# 1541-3m.net
KiCad netlist of a schematic drawn in EAGLE
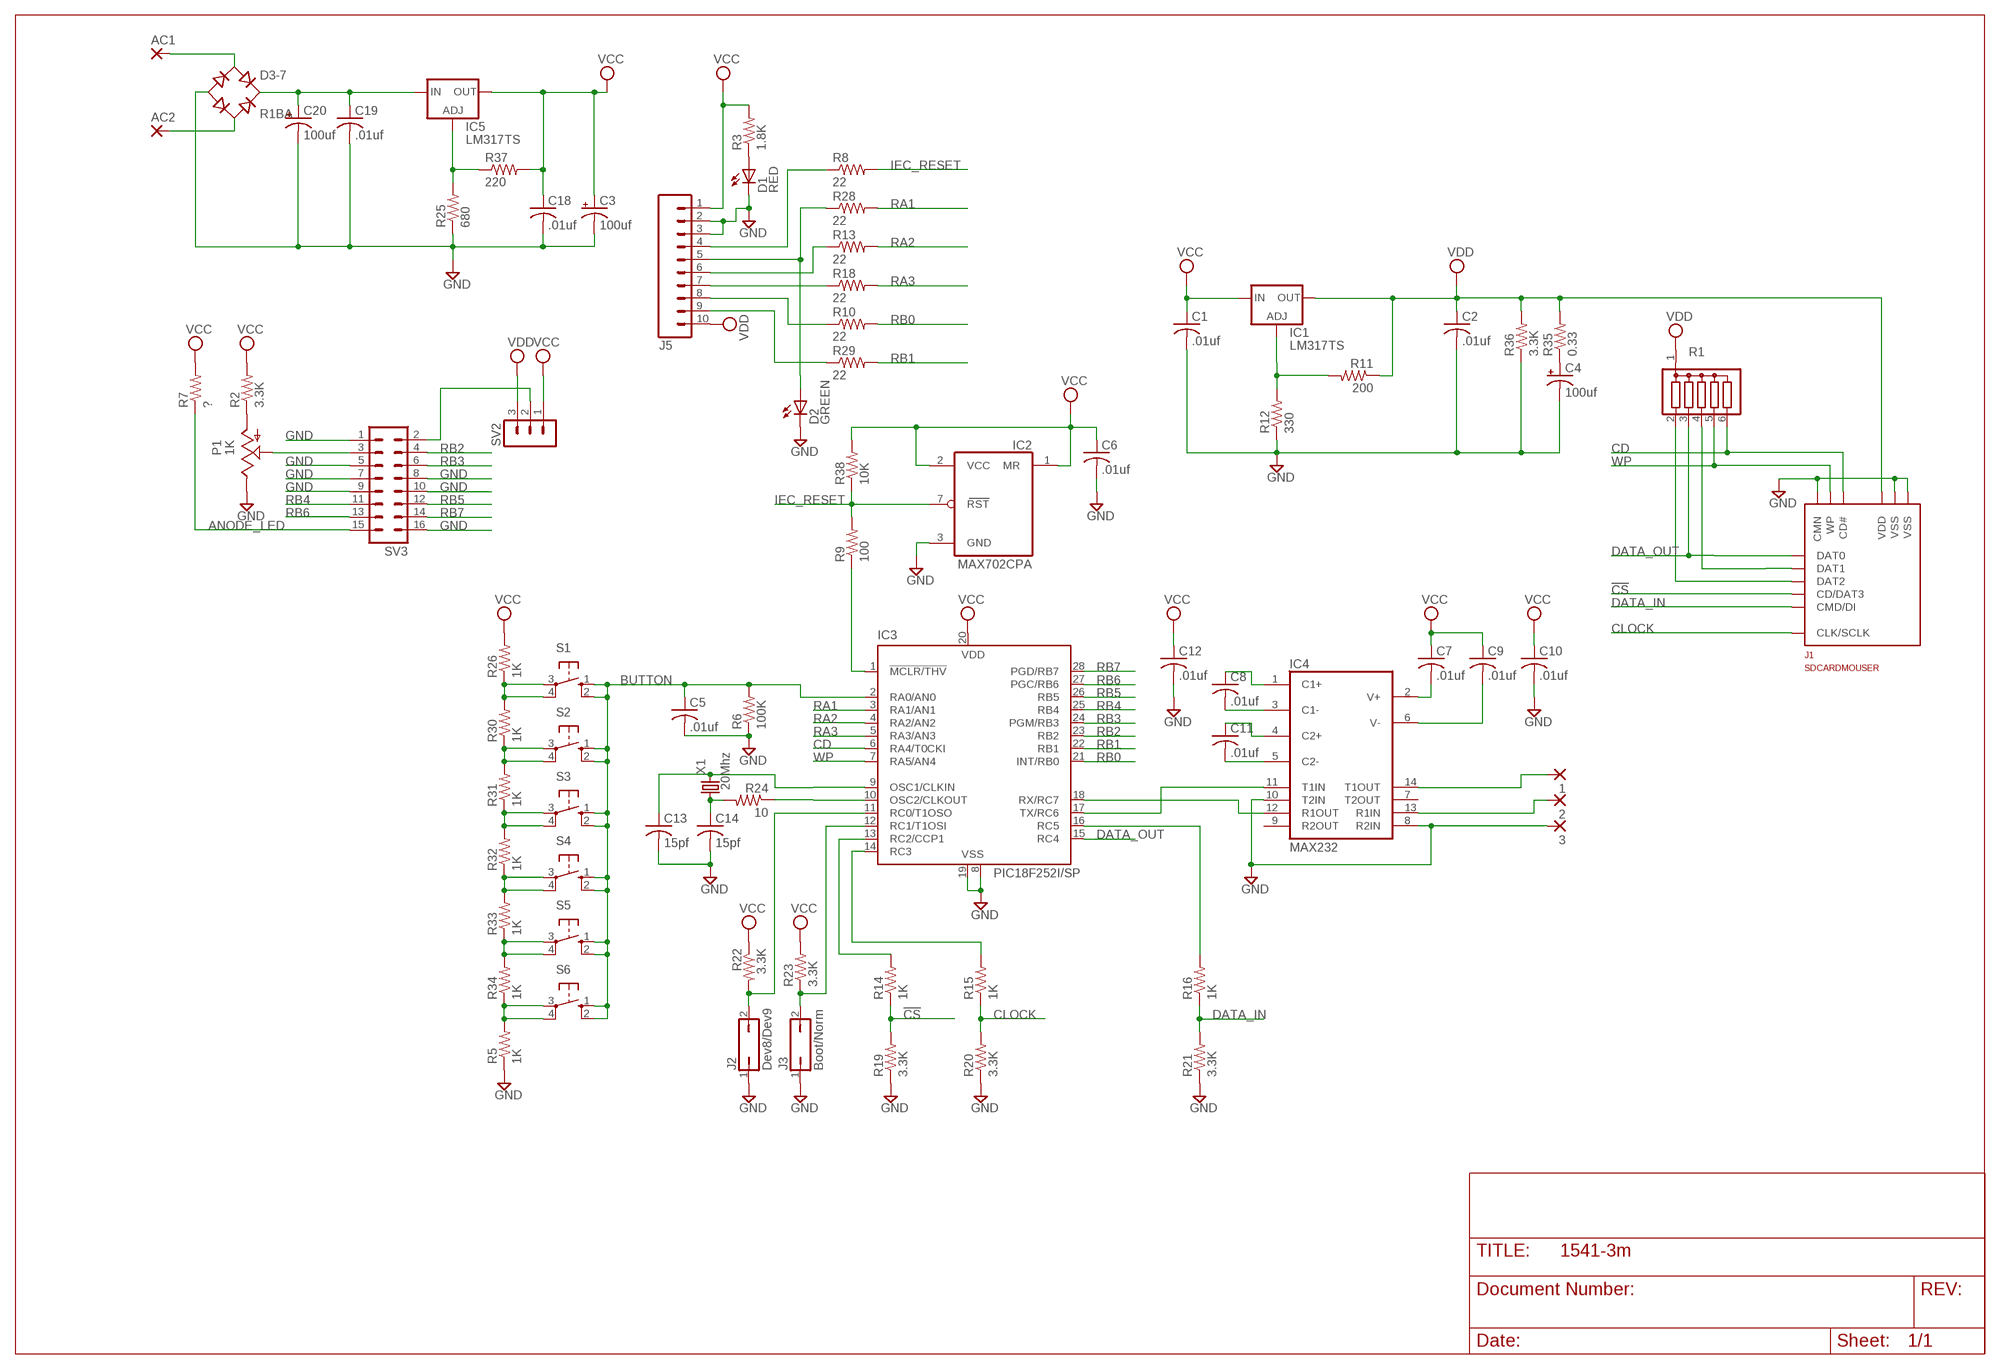
[diagram p0: schematic, sheet 1]

(export (version "E")
  (design (tool "Eeschema 10.0.6"))
  (components
    (comp (ref "1")
      (value "2,15/1,0")
      (footprint "eagle-import:2,15_1,0")
      (libsource (lib "eagle-import") (part "2,15/1,0"))
    )
    (comp (ref "2")
      (value "2,15/1,0")
      (footprint "eagle-import:2,15_1,0")
      (libsource (lib "eagle-import") (part "2,15/1,0"))
    )
    (comp (ref "3")
      (value "2,15/1,0")
      (footprint "eagle-import:2,15_1,0")
      (libsource (lib "eagle-import") (part "2,15/1,0"))
    )
    (comp (ref "AC1")
      (value "2,15/1,0")
      (footprint "eagle-import:2,15_1,0")
      (libsource (lib "eagle-import") (part "2,15/1,0"))
    )
    (comp (ref "AC2")
      (value "2,15/1,0")
      (footprint "eagle-import:2,15_1,0")
      (libsource (lib "eagle-import") (part "2,15/1,0"))
    )
    (comp (ref "C1")
      (value ".01uf")
      (footprint "eagle-import:C025-024X044")
      (libsource (lib "eagle-import") (part "C-US025-024X044"))
    )
    (comp (ref "C2")
      (value ".01uf")
      (footprint "eagle-import:C025-024X044")
      (libsource (lib "eagle-import") (part "C-US025-024X044"))
    )
    (comp (ref "C3")
      (value "100uf")
      (footprint "eagle-import:E2-5")
      (libsource (lib "eagle-import") (part "CPOL-USE2-5"))
    )
    (comp (ref "C4")
      (value "100uf")
      (footprint "eagle-import:E2-5")
      (libsource (lib "eagle-import") (part "CPOL-USE2-5"))
    )
    (comp (ref "C5")
      (value ".01uf")
      (footprint "eagle-import:C025-024X044")
      (libsource (lib "eagle-import") (part "C-US025-024X044"))
    )
    (comp (ref "C6")
      (value ".01uf")
      (footprint "eagle-import:C025-024X044")
      (libsource (lib "eagle-import") (part "C-US025-024X044"))
    )
    (comp (ref "C7")
      (value ".01uf")
      (footprint "eagle-import:C025-024X044")
      (libsource (lib "eagle-import") (part "C-US025-024X044"))
    )
    (comp (ref "C8")
      (value ".01uf")
      (footprint "eagle-import:C025-024X044")
      (libsource (lib "eagle-import") (part "C-US025-024X044"))
    )
    (comp (ref "C9")
      (value ".01uf")
      (footprint "eagle-import:C025-024X044")
      (libsource (lib "eagle-import") (part "C-US025-024X044"))
    )
    (comp (ref "C10")
      (value ".01uf")
      (footprint "eagle-import:C025-024X044")
      (libsource (lib "eagle-import") (part "C-US025-024X044"))
    )
    (comp (ref "C11")
      (value ".01uf")
      (footprint "eagle-import:C025-024X044")
      (libsource (lib "eagle-import") (part "C-US025-024X044"))
    )
    (comp (ref "C12")
      (value ".01uf")
      (footprint "eagle-import:C025-024X044")
      (libsource (lib "eagle-import") (part "C-US025-024X044"))
    )
    (comp (ref "C13")
      (value "15pf")
      (footprint "eagle-import:C025-024X044")
      (libsource (lib "eagle-import") (part "C-US025-024X044"))
    )
    (comp (ref "C14")
      (value "15pf")
      (footprint "eagle-import:C025-024X044")
      (libsource (lib "eagle-import") (part "C-US025-024X044"))
    )
    (comp (ref "C18")
      (value ".01uf")
      (footprint "eagle-import:C025-024X044")
      (libsource (lib "eagle-import") (part "C-US025-024X044"))
    )
    (comp (ref "C19")
      (value ".01uf")
      (footprint "eagle-import:C025-024X044")
      (libsource (lib "eagle-import") (part "C-US025-024X044"))
    )
    (comp (ref "C20")
      (value "100uf")
      (footprint "eagle-import:E2-5")
      (libsource (lib "eagle-import") (part "CPOL-USE2-5"))
    )
    (comp (ref "D1")
      (value "RED")
      (footprint "eagle-import:LED3MM")
      (libsource (lib "eagle-import") (part "LED3MM"))
    )
    (comp (ref "D2")
      (value "GREEN")
      (footprint "eagle-import:LED3MM")
      (libsource (lib "eagle-import") (part "LED3MM"))
    )
    (comp (ref "D3-7")
      (value "R1BA")
      (footprint "eagle-import:RB1A")
      (libsource (lib "eagle-import") (part "RB1A"))
    )
    (comp (ref "IC1")
      (value "LM317TS")
      (footprint "eagle-import:317TS")
      (libsource (lib "eagle-import") (part "LM317TS"))
    )
    (comp (ref "IC2")
      (value "MAX702CPA")
      (footprint "eagle-import:DIL08")
      (fields (field (name "MF") "MAXIM") (field (name "MPN") "MAX702CPA+"))
      (libsource (lib "eagle-import") (part "MAX702CPA"))
    )
    (comp (ref "IC3")
      (value "PIC18F252I/SP")
      (footprint "eagle-import:DIL28-3")
      (fields (field (name "MF") "MICROCHIP") (field (name "MPN") "PIC16F870-I/SP"))
      (libsource (lib "eagle-import") (part "PIC16870PF"))
    )
    (comp (ref "IC4")
      (value "MAX232")
      (footprint "eagle-import:DIL16")
      (fields (field (name "MF") "MAXIM") (field (name "MPN") "MAX232ACPE+"))
      (libsource (lib "eagle-import") (part "MAX232"))
    )
    (comp (ref "IC5")
      (value "LM317TS")
      (footprint "eagle-import:317TS")
      (libsource (lib "eagle-import") (part "LM317TS"))
    )
    (comp (ref "J1")
      (value "SDCARDMOUSER")
      (footprint "eagle-import:SCDA1A")
      (libsource (lib "eagle-import") (part "SDCARDMOUSER"))
    )
    (comp (ref "J2")
      (value "Dev8/Dev9")
      (footprint "eagle-import:JP1")
      (libsource (lib "eagle-import") (part "JP1Q"))
    )
    (comp (ref "J3")
      (value "Boot/Norm")
      (footprint "eagle-import:JP1")
      (libsource (lib "eagle-import") (part "JP1Q"))
    )
    (comp (ref "J5")
      (value "M10")
      (footprint "eagle-import:10P")
      (libsource (lib "eagle-import") (part "M10"))
    )
    (comp (ref "P1")
      (value "1K")
      (footprint "eagle-import:LI10")
      (libsource (lib "eagle-import") (part "TRIM_US-LI10"))
    )
    (comp (ref "R1")
      (value "G05R")
      (footprint "eagle-import:SIL6")
      (libsource (lib "eagle-import") (part "G05R"))
    )
    (comp (ref "R2")
      (value "3.3K")
      (footprint "eagle-import:0207_2V")
      (libsource (lib "eagle-import") (part "R-US_0207/2V"))
    )
    (comp (ref "R3")
      (value "1.8K")
      (footprint "eagle-import:0207_2V")
      (libsource (lib "eagle-import") (part "R-US_0207/2V"))
    )
    (comp (ref "R5")
      (value "1K")
      (footprint "eagle-import:0207_2V")
      (libsource (lib "eagle-import") (part "R-US_0207/2V"))
    )
    (comp (ref "R6")
      (value "100K")
      (footprint "eagle-import:0207_2V")
      (libsource (lib "eagle-import") (part "R-US_0207/2V"))
    )
    (comp (ref "R7")
      (value "?")
      (footprint "eagle-import:0207_2V")
      (libsource (lib "eagle-import") (part "R-US_0207/2V"))
    )
    (comp (ref "R8")
      (value "22")
      (footprint "eagle-import:0207_2V")
      (libsource (lib "eagle-import") (part "R-US_0207/2V"))
    )
    (comp (ref "R9")
      (value "100")
      (footprint "eagle-import:0207_2V")
      (libsource (lib "eagle-import") (part "R-US_0207/2V"))
    )
    (comp (ref "R10")
      (value "22")
      (footprint "eagle-import:0207_2V")
      (libsource (lib "eagle-import") (part "R-US_0207/2V"))
    )
    (comp (ref "R11")
      (value "200")
      (footprint "eagle-import:0207_2V")
      (libsource (lib "eagle-import") (part "R-US_0207/2V"))
    )
    (comp (ref "R12")
      (value "330")
      (footprint "eagle-import:0207_2V")
      (libsource (lib "eagle-import") (part "R-US_0207/2V"))
    )
    (comp (ref "R13")
      (value "22")
      (footprint "eagle-import:0207_2V")
      (libsource (lib "eagle-import") (part "R-US_0207/2V"))
    )
    (comp (ref "R14")
      (value "1K")
      (footprint "eagle-import:0207_2V")
      (libsource (lib "eagle-import") (part "R-US_0207/2V"))
    )
    (comp (ref "R15")
      (value "1K")
      (footprint "eagle-import:0207_2V")
      (libsource (lib "eagle-import") (part "R-US_0207/2V"))
    )
    (comp (ref "R16")
      (value "1K")
      (footprint "eagle-import:0207_2V")
      (libsource (lib "eagle-import") (part "R-US_0207/2V"))
    )
    (comp (ref "R18")
      (value "22")
      (footprint "eagle-import:0207_2V")
      (libsource (lib "eagle-import") (part "R-US_0207/2V"))
    )
    (comp (ref "R19")
      (value "3.3K")
      (footprint "eagle-import:0207_2V")
      (libsource (lib "eagle-import") (part "R-US_0207/2V"))
    )
    (comp (ref "R20")
      (value "3.3K")
      (footprint "eagle-import:0207_2V")
      (libsource (lib "eagle-import") (part "R-US_0207/2V"))
    )
    (comp (ref "R21")
      (value "3.3K")
      (footprint "eagle-import:0207_2V")
      (libsource (lib "eagle-import") (part "R-US_0207/2V"))
    )
    (comp (ref "R22")
      (value "3.3K")
      (footprint "eagle-import:0207_2V")
      (libsource (lib "eagle-import") (part "R-US_0207/2V"))
    )
    (comp (ref "R23")
      (value "3.3K")
      (footprint "eagle-import:0207_2V")
      (libsource (lib "eagle-import") (part "R-US_0207/2V"))
    )
    (comp (ref "R24")
      (value "10")
      (footprint "eagle-import:0207_2V")
      (libsource (lib "eagle-import") (part "R-US_0207/2V"))
    )
    (comp (ref "R25")
      (value "680")
      (footprint "eagle-import:0207_2V")
      (libsource (lib "eagle-import") (part "R-US_0207/2V"))
    )
    (comp (ref "R26")
      (value "1K")
      (footprint "eagle-import:0207_2V")
      (libsource (lib "eagle-import") (part "R-US_0207/2V"))
    )
    (comp (ref "R28")
      (value "22")
      (footprint "eagle-import:0207_2V")
      (libsource (lib "eagle-import") (part "R-US_0207/2V"))
    )
    (comp (ref "R29")
      (value "22")
      (footprint "eagle-import:0207_2V")
      (libsource (lib "eagle-import") (part "R-US_0207/2V"))
    )
    (comp (ref "R30")
      (value "1K")
      (footprint "eagle-import:0207_2V")
      (libsource (lib "eagle-import") (part "R-US_0207/2V"))
    )
    (comp (ref "R31")
      (value "1K")
      (footprint "eagle-import:0207_2V")
      (libsource (lib "eagle-import") (part "R-US_0207/2V"))
    )
    (comp (ref "R32")
      (value "1K")
      (footprint "eagle-import:0207_2V")
      (libsource (lib "eagle-import") (part "R-US_0207/2V"))
    )
    (comp (ref "R33")
      (value "1K")
      (footprint "eagle-import:0207_2V")
      (libsource (lib "eagle-import") (part "R-US_0207/2V"))
    )
    (comp (ref "R34")
      (value "1K")
      (footprint "eagle-import:0207_2V")
      (libsource (lib "eagle-import") (part "R-US_0207/2V"))
    )
    (comp (ref "R35")
      (value "0.33")
      (footprint "eagle-import:0207_2V")
      (libsource (lib "eagle-import") (part "R-US_0207/2V"))
    )
    (comp (ref "R36")
      (value "3.3K")
      (footprint "eagle-import:0207_2V")
      (libsource (lib "eagle-import") (part "R-US_0207/2V"))
    )
    (comp (ref "R37")
      (value "220")
      (footprint "eagle-import:0207_2V")
      (libsource (lib "eagle-import") (part "R-US_0207/2V"))
    )
    (comp (ref "R38")
      (value "10K")
      (footprint "eagle-import:0207_2V")
      (libsource (lib "eagle-import") (part "R-US_0207/2V"))
    )
    (comp (ref "S1")
      (value "10-XX")
      (footprint "eagle-import:B3F-10XX")
      (fields (field (name "MPN") "B3F-1000"))
      (libsource (lib "eagle-import") (part "10-XX"))
    )
    (comp (ref "S2")
      (value "10-XX")
      (footprint "eagle-import:B3F-10XX")
      (fields (field (name "MPN") "B3F-1000"))
      (libsource (lib "eagle-import") (part "10-XX"))
    )
    (comp (ref "S3")
      (value "10-XX")
      (footprint "eagle-import:B3F-10XX")
      (fields (field (name "MPN") "B3F-1000"))
      (libsource (lib "eagle-import") (part "10-XX"))
    )
    (comp (ref "S4")
      (value "10-XX")
      (footprint "eagle-import:B3F-10XX")
      (fields (field (name "MPN") "B3F-1000"))
      (libsource (lib "eagle-import") (part "10-XX"))
    )
    (comp (ref "S5")
      (value "10-XX")
      (footprint "eagle-import:B3F-10XX")
      (fields (field (name "MPN") "B3F-1000"))
      (libsource (lib "eagle-import") (part "10-XX"))
    )
    (comp (ref "S6")
      (value "10-XX")
      (footprint "eagle-import:B3F-10XX")
      (fields (field (name "MPN") "B3F-1000"))
      (libsource (lib "eagle-import") (part "10-XX"))
    )
    (comp (ref "SV2")
      (value "MA03-1")
      (footprint "eagle-import:MA03-1")
      (libsource (lib "eagle-import") (part "MA03-1"))
    )
    (comp (ref "SV3")
      (value "ML16")
      (footprint "eagle-import:ML16")
      (libsource (lib "eagle-import") (part "ML16"))
    )
    (comp (ref "X1")
      (value "20Mhz")
      (footprint "eagle-import:HC49U70")
      (libsource (lib "eagle-import") (part "CRYSTALHC49U70"))
    )
  )
  (nets
    (net (code "1") (name "/ANODE_LED") (class "Default")
      (node (ref "R7") (pin "1") (pinfunction "1_1") (pintype "passive"))
      (node (ref "SV3") (pin "15") (pinfunction "15_15") (pintype "passive"))
    )
    (net (code "2") (name "/BUTTON") (class "Default")
      (node (ref "C5") (pin "1") (pinfunction "1_1") (pintype "passive"))
      (node (ref "IC3") (pin "2") (pinfunction "RA0/AN0_2") (pintype "bidirectional"))
      (node (ref "R6") (pin "2") (pinfunction "2_2") (pintype "passive"))
      (node (ref "S1") (pin "1") (pinfunction "S_1") (pintype "passive"))
      (node (ref "S1") (pin "2") (pinfunction "S1_2") (pintype "passive"))
      (node (ref "S2") (pin "1") (pinfunction "S_1") (pintype "passive"))
      (node (ref "S2") (pin "2") (pinfunction "S1_2") (pintype "passive"))
      (node (ref "S3") (pin "1") (pinfunction "S_1") (pintype "passive"))
      (node (ref "S3") (pin "2") (pinfunction "S1_2") (pintype "passive"))
      (node (ref "S4") (pin "1") (pinfunction "S_1") (pintype "passive"))
      (node (ref "S4") (pin "2") (pinfunction "S1_2") (pintype "passive"))
      (node (ref "S5") (pin "1") (pinfunction "S_1") (pintype "passive"))
      (node (ref "S5") (pin "2") (pinfunction "S1_2") (pintype "passive"))
      (node (ref "S6") (pin "1") (pinfunction "S_1") (pintype "passive"))
      (node (ref "S6") (pin "2") (pinfunction "S1_2") (pintype "passive"))
    )
    (net (code "3") (name "/CD") (class "Default")
      (node (ref "IC3") (pin "6") (pinfunction "RA4/T0CKI_6") (pintype "bidirectional"))
      (node (ref "J1") (pin "10") (pinfunction "CD#_10") (pintype "output"))
      (node (ref "R1") (pin "6") (pinfunction "6_6") (pintype "passive"))
    )
    (net (code "4") (name "/CLOCK") (class "Default")
      (node (ref "J1") (pin "5") (pinfunction "CLK/SCLK_5") (pintype "bidirectional"))
      (node (ref "R15") (pin "1") (pinfunction "1_1") (pintype "passive"))
      (node (ref "R20") (pin "2") (pinfunction "2_2") (pintype "passive"))
    )
    (net (code "5") (name "/DATA_IN") (class "Default")
      (node (ref "J1") (pin "2") (pinfunction "CMD/DI_2") (pintype "bidirectional"))
      (node (ref "R16") (pin "1") (pinfunction "1_1") (pintype "passive"))
      (node (ref "R21") (pin "2") (pinfunction "2_2") (pintype "passive"))
    )
    (net (code "6") (name "/DATA_OUT") (class "Default")
      (node (ref "IC3") (pin "15") (pinfunction "RC4_15") (pintype "bidirectional"))
      (node (ref "J1") (pin "7") (pinfunction "DAT0_7") (pintype "bidirectional"))
      (node (ref "R1") (pin "3") (pinfunction "3_3") (pintype "passive"))
    )
    (net (code "7") (name "/IEC_RESET") (class "Default")
      (node (ref "IC2") (pin "7") (pinfunction "RST_7") (pintype "output"))
      (node (ref "R38") (pin "1") (pinfunction "1_1") (pintype "passive"))
      (node (ref "R8") (pin "2") (pinfunction "2_2") (pintype "passive"))
      (node (ref "R9") (pin "2") (pinfunction "2_2") (pintype "passive"))
    )
    (net (code "8") (name "/RA1") (class "Default")
      (node (ref "IC3") (pin "3") (pinfunction "RA1/AN1_3") (pintype "bidirectional"))
      (node (ref "R28") (pin "2") (pinfunction "2_2") (pintype "passive"))
    )
    (net (code "9") (name "/RA2") (class "Default")
      (node (ref "IC3") (pin "4") (pinfunction "RA2/AN2_4") (pintype "bidirectional"))
      (node (ref "R13") (pin "2") (pinfunction "2_2") (pintype "passive"))
    )
    (net (code "10") (name "/RA3") (class "Default")
      (node (ref "IC3") (pin "5") (pinfunction "RA3/AN3_5") (pintype "bidirectional"))
      (node (ref "R18") (pin "2") (pinfunction "2_2") (pintype "passive"))
    )
    (net (code "11") (name "/RB0") (class "Default")
      (node (ref "IC3") (pin "21") (pinfunction "INT/RB0_21") (pintype "bidirectional"))
      (node (ref "R10") (pin "2") (pinfunction "2_2") (pintype "passive"))
    )
    (net (code "12") (name "/RB1") (class "Default")
      (node (ref "IC3") (pin "22") (pinfunction "RB1_22") (pintype "bidirectional"))
      (node (ref "R29") (pin "2") (pinfunction "2_2") (pintype "passive"))
    )
    (net (code "13") (name "/RB2") (class "Default")
      (node (ref "IC3") (pin "23") (pinfunction "RB2_23") (pintype "bidirectional"))
      (node (ref "SV3") (pin "4") (pinfunction "4_4") (pintype "passive"))
    )
    (net (code "14") (name "/RB3") (class "Default")
      (node (ref "IC3") (pin "24") (pinfunction "PGM/RB3_24") (pintype "bidirectional"))
      (node (ref "SV3") (pin "6") (pinfunction "6_6") (pintype "passive"))
    )
    (net (code "15") (name "/RB4") (class "Default")
      (node (ref "IC3") (pin "25") (pinfunction "RB4_25") (pintype "bidirectional"))
      (node (ref "SV3") (pin "11") (pinfunction "11_11") (pintype "passive"))
    )
    (net (code "16") (name "/RB5") (class "Default")
      (node (ref "IC3") (pin "26") (pinfunction "RB5_26") (pintype "bidirectional"))
      (node (ref "SV3") (pin "12") (pinfunction "12_12") (pintype "passive"))
    )
    (net (code "17") (name "/RB6") (class "Default")
      (node (ref "IC3") (pin "27") (pinfunction "PGC/RB6_27") (pintype "bidirectional"))
      (node (ref "SV3") (pin "13") (pinfunction "13_13") (pintype "passive"))
    )
    (net (code "18") (name "/RB7") (class "Default")
      (node (ref "IC3") (pin "28") (pinfunction "PGD/RB7_28") (pintype "bidirectional"))
      (node (ref "SV3") (pin "14") (pinfunction "14_14") (pintype "passive"))
    )
    (net (code "19") (name "/WP") (class "Default")
      (node (ref "IC3") (pin "7") (pinfunction "RA5/AN4_7") (pintype "bidirectional"))
      (node (ref "J1") (pin "12") (pinfunction "WP_12") (pintype "output"))
      (node (ref "R1") (pin "5") (pinfunction "5_5") (pintype "passive"))
    )
    (net (code "20") (name "/~{CS}") (class "Default")
      (node (ref "J1") (pin "1") (pinfunction "CD/DAT3_1") (pintype "bidirectional"))
      (node (ref "R14") (pin "1") (pinfunction "1_1") (pintype "passive"))
      (node (ref "R19") (pin "2") (pinfunction "2_2") (pintype "passive"))
    )
    (net (code "21") (name "GND") (class "Default")
      (node (ref "3") (pin "1") (pinfunction "P_1") (pintype "passive"))
      (node (ref "C1") (pin "2") (pinfunction "2_2") (pintype "passive"))
      (node (ref "C10") (pin "2") (pinfunction "2_2") (pintype "passive"))
      (node (ref "C12") (pin "2") (pinfunction "2_2") (pintype "passive"))
      (node (ref "C13") (pin "2") (pinfunction "2_2") (pintype "passive"))
      (node (ref "C14") (pin "2") (pinfunction "2_2") (pintype "passive"))
      (node (ref "C18") (pin "2") (pinfunction "2_2") (pintype "passive"))
      (node (ref "C19") (pin "2") (pinfunction "2_2") (pintype "passive"))
      (node (ref "C2") (pin "2") (pinfunction "2_2") (pintype "passive"))
      (node (ref "C20") (pin "-") (pinfunction "-_-") (pintype "passive"))
      (node (ref "C3") (pin "-") (pinfunction "-_-") (pintype "passive"))
      (node (ref "C4") (pin "-") (pinfunction "-_-") (pintype "passive"))
      (node (ref "C5") (pin "2") (pinfunction "2_2") (pintype "passive"))
      (node (ref "C6") (pin "2") (pinfunction "2_2") (pintype "passive"))
      (node (ref "D1") (pin "K") (pinfunction "C_K") (pintype "passive"))
      (node (ref "D2") (pin "K") (pinfunction "C_K") (pintype "passive"))
      (node (ref "D3-7") (pin "-") (pinfunction "-_-") (pintype "passive"))
      (node (ref "IC2") (pin "3") (pinfunction "GND_3") (pintype "power_in"))
      (node (ref "IC3") (pin "19") (pinfunction "VSS_19") (pintype "power_in"))
      (node (ref "IC3") (pin "8") (pinfunction "VSS_8") (pintype "power_in"))
      (node (ref "IC4") (pin "10") (pinfunction "T2IN_10") (pintype "input"))
      (node (ref "IC4") (pin "8") (pinfunction "R2IN_8") (pintype "input"))
      (node (ref "J1") (pin "11") (pinfunction "CMN_11") (pintype "input"))
      (node (ref "J1") (pin "3") (pinfunction "VSS_3") (pintype "power_in"))
      (node (ref "J1") (pin "6") (pinfunction "VSS_6") (pintype "power_in"))
      (node (ref "J2") (pin "1") (pinfunction "1_1") (pintype "passive"))
      (node (ref "J3") (pin "1") (pinfunction "1_1") (pintype "passive"))
      (node (ref "J5") (pin "2") (pinfunction "2_2") (pintype "passive"))
      (node (ref "J5") (pin "3") (pinfunction "3_3") (pintype "passive"))
      (node (ref "P1") (pin "E") (pinfunction "E_E") (pintype "passive"))
      (node (ref "R12") (pin "1") (pinfunction "1_1") (pintype "passive"))
      (node (ref "R19") (pin "1") (pinfunction "1_1") (pintype "passive"))
      (node (ref "R20") (pin "1") (pinfunction "1_1") (pintype "passive"))
      (node (ref "R21") (pin "1") (pinfunction "1_1") (pintype "passive"))
      (node (ref "R25") (pin "1") (pinfunction "1_1") (pintype "passive"))
      (node (ref "R36") (pin "1") (pinfunction "1_1") (pintype "passive"))
      (node (ref "R5") (pin "1") (pinfunction "1_1") (pintype "passive"))
      (node (ref "R6") (pin "1") (pinfunction "1_1") (pintype "passive"))
      (node (ref "SV3") (pin "1") (pinfunction "1_1") (pintype "passive"))
      (node (ref "SV3") (pin "10") (pinfunction "10_10") (pintype "passive"))
      (node (ref "SV3") (pin "16") (pinfunction "16_16") (pintype "passive"))
      (node (ref "SV3") (pin "5") (pinfunction "5_5") (pintype "passive"))
      (node (ref "SV3") (pin "7") (pinfunction "7_7") (pintype "passive"))
      (node (ref "SV3") (pin "8") (pinfunction "8_8") (pintype "passive"))
      (node (ref "SV3") (pin "9") (pinfunction "9_9") (pintype "passive"))
    )
    (net (code "22") (name "Net-(1-P)") (class "Default")
      (node (ref "1") (pin "1") (pinfunction "P_1") (pintype "passive"))
      (node (ref "IC4") (pin "14") (pinfunction "T1OUT_14") (pintype "output"))
    )
    (net (code "23") (name "Net-(2-P)") (class "Default")
      (node (ref "2") (pin "1") (pinfunction "P_1") (pintype "passive"))
      (node (ref "IC4") (pin "13") (pinfunction "R1IN_13") (pintype "input"))
    )
    (net (code "24") (name "Net-(AC1-P)") (class "Default")
      (node (ref "AC1") (pin "1") (pinfunction "P_1") (pintype "passive"))
      (node (ref "D3-7") (pin "AC1") (pinfunction "AC1_AC1") (pintype "passive"))
    )
    (net (code "25") (name "Net-(AC2-P)") (class "Default")
      (node (ref "AC2") (pin "1") (pinfunction "P_1") (pintype "passive"))
      (node (ref "D3-7") (pin "AC2") (pinfunction "AC2_AC2") (pintype "passive"))
    )
    (net (code "26") (name "Net-(C4-Pad+)") (class "Default")
      (node (ref "C4") (pin "+") (pinfunction "+_+") (pintype "passive"))
      (node (ref "R35") (pin "1") (pinfunction "1_1") (pintype "passive"))
    )
    (net (code "27") (name "Net-(C14-Pad1)") (class "Default")
      (node (ref "C14") (pin "1") (pinfunction "1_1") (pintype "passive"))
      (node (ref "R24") (pin "2") (pinfunction "2_2") (pintype "passive"))
      (node (ref "X1") (pin "1") (pinfunction "1_1") (pintype "passive"))
    )
    (net (code "28") (name "Net-(D1-PadA)") (class "Default")
      (node (ref "D1") (pin "A") (pinfunction "A_A") (pintype "passive"))
      (node (ref "R3") (pin "1") (pinfunction "1_1") (pintype "passive"))
    )
    (net (code "29") (name "Net-(D2-PadA)") (class "Default")
      (node (ref "D2") (pin "A") (pinfunction "A_A") (pintype "passive"))
      (node (ref "J5") (pin "5") (pinfunction "5_5") (pintype "passive"))
      (node (ref "R28") (pin "1") (pinfunction "1_1") (pintype "passive"))
    )
    (net (code "30") (name "Net-(IC1-ADJ)") (class "Default")
      (node (ref "IC1") (pin "1") (pinfunction "ADJ_1") (pintype "input"))
      (node (ref "R11") (pin "2") (pinfunction "2_2") (pintype "passive"))
      (node (ref "R12") (pin "2") (pinfunction "2_2") (pintype "passive"))
    )
    (net (code "31") (name "Net-(IC3-OSC1{slash}CLKIN)") (class "Default")
      (node (ref "C13") (pin "1") (pinfunction "1_1") (pintype "passive"))
      (node (ref "IC3") (pin "9") (pinfunction "OSC1/CLKIN_9") (pintype "input"))
      (node (ref "X1") (pin "2") (pinfunction "2_2") (pintype "passive"))
    )
    (net (code "32") (name "Net-(IC3-OSC2{slash}CLKOUT)") (class "Default")
      (node (ref "IC3") (pin "10") (pinfunction "OSC2/CLKOUT_10") (pintype "output"))
      (node (ref "R24") (pin "1") (pinfunction "1_1") (pintype "passive"))
    )
    (net (code "33") (name "Net-(IC3-RC0{slash}T1OSO)") (class "Default")
      (node (ref "IC3") (pin "11") (pinfunction "RC0/T1OSO_11") (pintype "bidirectional"))
      (node (ref "J2") (pin "2") (pinfunction "2_2") (pintype "passive"))
      (node (ref "R22") (pin "2") (pinfunction "2_2") (pintype "passive"))
    )
    (net (code "34") (name "Net-(IC3-RC1{slash}T1OSI)") (class "Default")
      (node (ref "IC3") (pin "12") (pinfunction "RC1/T1OSI_12") (pintype "bidirectional"))
      (node (ref "J3") (pin "2") (pinfunction "2_2") (pintype "passive"))
      (node (ref "R23") (pin "1") (pinfunction "1_1") (pintype "passive"))
    )
    (net (code "35") (name "Net-(IC3-RC2{slash}CCP1)") (class "Default")
      (node (ref "IC3") (pin "13") (pinfunction "RC2/CCP1_13") (pintype "bidirectional"))
      (node (ref "R14") (pin "2") (pinfunction "2_2") (pintype "passive"))
    )
    (net (code "36") (name "Net-(IC3-RC3)") (class "Default")
      (node (ref "IC3") (pin "14") (pinfunction "RC3_14") (pintype "bidirectional"))
      (node (ref "R15") (pin "2") (pinfunction "2_2") (pintype "passive"))
    )
    (net (code "37") (name "Net-(IC3-RC5)") (class "Default")
      (node (ref "IC3") (pin "16") (pinfunction "RC5_16") (pintype "bidirectional"))
      (node (ref "R16") (pin "2") (pinfunction "2_2") (pintype "passive"))
    )
    (net (code "38") (name "Net-(IC3-RX{slash}RC7)") (class "Default")
      (node (ref "IC3") (pin "18") (pinfunction "RX/RC7_18") (pintype "bidirectional"))
      (node (ref "IC4") (pin "12") (pinfunction "R1OUT_12") (pintype "output"))
    )
    (net (code "39") (name "Net-(IC3-TX{slash}RC6)") (class "Default")
      (node (ref "IC3") (pin "17") (pinfunction "TX/RC6_17") (pintype "bidirectional"))
      (node (ref "IC4") (pin "11") (pinfunction "T1IN_11") (pintype "input"))
    )
    (net (code "40") (name "Net-(IC3-~{MCLR{slash}THV})") (class "Default")
      (node (ref "IC3") (pin "1") (pinfunction "~{MCLR/THV}_1") (pintype "input"))
      (node (ref "R9") (pin "1") (pinfunction "1_1") (pintype "passive"))
    )
    (net (code "41") (name "Net-(IC4A-C1+)") (class "Default")
      (node (ref "C8") (pin "1") (pinfunction "1_1") (pintype "passive"))
      (node (ref "IC4") (pin "1") (pinfunction "C1+_1") (pintype "bidirectional"))
    )
    (net (code "42") (name "Net-(IC4A-C1-)") (class "Default")
      (node (ref "C8") (pin "2") (pinfunction "2_2") (pintype "passive"))
      (node (ref "IC4") (pin "3") (pinfunction "C1-_3") (pintype "bidirectional"))
    )
    (net (code "43") (name "Net-(IC4A-C2+)") (class "Default")
      (node (ref "C11") (pin "1") (pinfunction "1_1") (pintype "passive"))
      (node (ref "IC4") (pin "4") (pinfunction "C2+_4") (pintype "bidirectional"))
    )
    (net (code "44") (name "Net-(IC4A-C2-)") (class "Default")
      (node (ref "C11") (pin "2") (pinfunction "2_2") (pintype "passive"))
      (node (ref "IC4") (pin "5") (pinfunction "C2-_5") (pintype "bidirectional"))
    )
    (net (code "45") (name "Net-(IC4A-V+)") (class "Default")
      (node (ref "C7") (pin "2") (pinfunction "2_2") (pintype "passive"))
      (node (ref "IC4") (pin "2") (pinfunction "V+_2") (pintype "bidirectional"))
    )
    (net (code "46") (name "Net-(IC4A-V-)") (class "Default")
      (node (ref "C9") (pin "2") (pinfunction "2_2") (pintype "passive"))
      (node (ref "IC4") (pin "6") (pinfunction "V-_6") (pintype "bidirectional"))
    )
    (net (code "47") (name "Net-(IC5-ADJ)") (class "Default")
      (node (ref "IC5") (pin "1") (pinfunction "ADJ_1") (pintype "input"))
      (node (ref "R25") (pin "2") (pinfunction "2_2") (pintype "passive"))
      (node (ref "R37") (pin "1") (pinfunction "1_1") (pintype "passive"))
    )
    (net (code "48") (name "Net-(IC5-IN)") (class "Default")
      (node (ref "C19") (pin "1") (pinfunction "1_1") (pintype "passive"))
      (node (ref "C20") (pin "+") (pinfunction "+_+") (pintype "passive"))
      (node (ref "D3-7") (pin "+") (pinfunction "+_+") (pintype "passive"))
      (node (ref "IC5") (pin "3") (pinfunction "IN_3") (pintype "input"))
    )
    (net (code "49") (name "Net-(J1A-DAT1)") (class "Default")
      (node (ref "J1") (pin "8") (pinfunction "DAT1_8") (pintype "bidirectional"))
      (node (ref "R1") (pin "4") (pinfunction "4_4") (pintype "passive"))
    )
    (net (code "50") (name "Net-(J1A-DAT2)") (class "Default")
      (node (ref "J1") (pin "9") (pinfunction "DAT2_9") (pintype "bidirectional"))
      (node (ref "R1") (pin "2") (pinfunction "2_2") (pintype "passive"))
    )
    (net (code "51") (name "Net-(J5-Pad4)") (class "Default")
      (node (ref "J5") (pin "4") (pinfunction "4_4") (pintype "passive"))
      (node (ref "R8") (pin "1") (pinfunction "1_1") (pintype "passive"))
    )
    (net (code "52") (name "Net-(J5-Pad6)") (class "Default")
      (node (ref "J5") (pin "6") (pinfunction "6_6") (pintype "passive"))
      (node (ref "R13") (pin "1") (pinfunction "1_1") (pintype "passive"))
    )
    (net (code "53") (name "Net-(J5-Pad7)") (class "Default")
      (node (ref "J5") (pin "7") (pinfunction "7_7") (pintype "passive"))
      (node (ref "R18") (pin "1") (pinfunction "1_1") (pintype "passive"))
    )
    (net (code "54") (name "Net-(J5-Pad8)") (class "Default")
      (node (ref "J5") (pin "8") (pinfunction "8_8") (pintype "passive"))
      (node (ref "R10") (pin "1") (pinfunction "1_1") (pintype "passive"))
    )
    (net (code "55") (name "Net-(J5-Pad9)") (class "Default")
      (node (ref "J5") (pin "9") (pinfunction "9_9") (pintype "passive"))
      (node (ref "R29") (pin "1") (pinfunction "1_1") (pintype "passive"))
    )
    (net (code "56") (name "Net-(P1-PadA)") (class "Default")
      (node (ref "P1") (pin "A") (pinfunction "A_A") (pintype "passive"))
      (node (ref "R2") (pin "1") (pinfunction "1_1") (pintype "passive"))
    )
    (net (code "57") (name "Net-(P1-PadS)") (class "Default")
      (node (ref "P1") (pin "S") (pinfunction "S_S") (pintype "passive"))
      (node (ref "SV3") (pin "3") (pinfunction "3_3") (pintype "passive"))
    )
    (net (code "58") (name "Net-(S1-P)") (class "Default")
      (node (ref "R26") (pin "1") (pinfunction "1_1") (pintype "passive"))
      (node (ref "R30") (pin "2") (pinfunction "2_2") (pintype "passive"))
      (node (ref "S1") (pin "3") (pinfunction "P_3") (pintype "passive"))
      (node (ref "S1") (pin "4") (pinfunction "P1_4") (pintype "passive"))
    )
    (net (code "59") (name "Net-(S2-P)") (class "Default")
      (node (ref "R30") (pin "1") (pinfunction "1_1") (pintype "passive"))
      (node (ref "R31") (pin "2") (pinfunction "2_2") (pintype "passive"))
      (node (ref "S2") (pin "3") (pinfunction "P_3") (pintype "passive"))
      (node (ref "S2") (pin "4") (pinfunction "P1_4") (pintype "passive"))
    )
    (net (code "60") (name "Net-(S3-P)") (class "Default")
      (node (ref "R31") (pin "1") (pinfunction "1_1") (pintype "passive"))
      (node (ref "R32") (pin "2") (pinfunction "2_2") (pintype "passive"))
      (node (ref "S3") (pin "3") (pinfunction "P_3") (pintype "passive"))
      (node (ref "S3") (pin "4") (pinfunction "P1_4") (pintype "passive"))
    )
    (net (code "61") (name "Net-(S4-P)") (class "Default")
      (node (ref "R32") (pin "1") (pinfunction "1_1") (pintype "passive"))
      (node (ref "R33") (pin "2") (pinfunction "2_2") (pintype "passive"))
      (node (ref "S4") (pin "3") (pinfunction "P_3") (pintype "passive"))
      (node (ref "S4") (pin "4") (pinfunction "P1_4") (pintype "passive"))
    )
    (net (code "62") (name "Net-(S5-P)") (class "Default")
      (node (ref "R33") (pin "1") (pinfunction "1_1") (pintype "passive"))
      (node (ref "R34") (pin "2") (pinfunction "2_2") (pintype "passive"))
      (node (ref "S5") (pin "3") (pinfunction "P_3") (pintype "passive"))
      (node (ref "S5") (pin "4") (pinfunction "P1_4") (pintype "passive"))
    )
    (net (code "63") (name "Net-(S6-P)") (class "Default")
      (node (ref "R34") (pin "1") (pinfunction "1_1") (pintype "passive"))
      (node (ref "R5") (pin "2") (pinfunction "2_2") (pintype "passive"))
      (node (ref "S6") (pin "3") (pinfunction "P_3") (pintype "passive"))
      (node (ref "S6") (pin "4") (pinfunction "P1_4") (pintype "passive"))
    )
    (net (code "64") (name "Net-(SV2-Pad2)") (class "Default")
      (node (ref "SV2") (pin "2") (pinfunction "2_2") (pintype "passive"))
      (node (ref "SV3") (pin "2") (pinfunction "2_2") (pintype "passive"))
    )
    (net (code "65") (name "VCC") (class "Default")
      (node (ref "C1") (pin "1") (pinfunction "1_1") (pintype "passive"))
      (node (ref "C10") (pin "1") (pinfunction "1_1") (pintype "passive"))
      (node (ref "C12") (pin "1") (pinfunction "1_1") (pintype "passive"))
      (node (ref "C18") (pin "1") (pinfunction "1_1") (pintype "passive"))
      (node (ref "C3") (pin "+") (pinfunction "+_+") (pintype "passive"))
      (node (ref "C6") (pin "1") (pinfunction "1_1") (pintype "passive"))
      (node (ref "C7") (pin "1") (pinfunction "1_1") (pintype "passive"))
      (node (ref "C9") (pin "1") (pinfunction "1_1") (pintype "passive"))
      (node (ref "IC1") (pin "3") (pinfunction "IN_3") (pintype "input"))
      (node (ref "IC2") (pin "1") (pinfunction "MR_1") (pintype "input"))
      (node (ref "IC2") (pin "2") (pinfunction "VCC_2") (pintype "power_in"))
      (node (ref "IC3") (pin "20") (pinfunction "VDD_20") (pintype "power_in"))
      (node (ref "IC5") (pin "2") (pinfunction "OUT_2") (pintype "passive"))
      (node (ref "J5") (pin "1") (pinfunction "1_1") (pintype "passive"))
      (node (ref "R2") (pin "2") (pinfunction "2_2") (pintype "passive"))
      (node (ref "R22") (pin "1") (pinfunction "1_1") (pintype "passive"))
      (node (ref "R23") (pin "2") (pinfunction "2_2") (pintype "passive"))
      (node (ref "R26") (pin "2") (pinfunction "2_2") (pintype "passive"))
      (node (ref "R3") (pin "2") (pinfunction "2_2") (pintype "passive"))
      (node (ref "R37") (pin "2") (pinfunction "2_2") (pintype "passive"))
      (node (ref "R38") (pin "2") (pinfunction "2_2") (pintype "passive"))
      (node (ref "R7") (pin "2") (pinfunction "2_2") (pintype "passive"))
      (node (ref "SV2") (pin "1") (pinfunction "1_1") (pintype "passive"))
    )
    (net (code "66") (name "VDD") (class "Default")
      (node (ref "C2") (pin "1") (pinfunction "1_1") (pintype "passive"))
      (node (ref "IC1") (pin "2") (pinfunction "OUT_2") (pintype "passive"))
      (node (ref "J1") (pin "4") (pinfunction "VDD_4") (pintype "power_in"))
      (node (ref "J5") (pin "10") (pinfunction "10_10") (pintype "passive"))
      (node (ref "R1") (pin "1") (pinfunction "1_1") (pintype "passive"))
      (node (ref "R11") (pin "1") (pinfunction "1_1") (pintype "passive"))
      (node (ref "R35") (pin "2") (pinfunction "2_2") (pintype "passive"))
      (node (ref "R36") (pin "2") (pinfunction "2_2") (pintype "passive"))
      (node (ref "SV2") (pin "3") (pinfunction "3_3") (pintype "passive"))
    )
    (net (code "67") (name "unconnected-(IC4A-R2OUT-Pad9)") (class "Default")
      (node (ref "IC4") (pin "9") (pinfunction "R2OUT_9") (pintype "output"))
    )
    (net (code "68") (name "unconnected-(IC4A-T2OUT-Pad7)") (class "Default")
      (node (ref "IC4") (pin "7") (pinfunction "T2OUT_7") (pintype "output"))
    )
  )
)
